# Mesure.net
KiCad netlist of a schematic drawn in Altium Designer
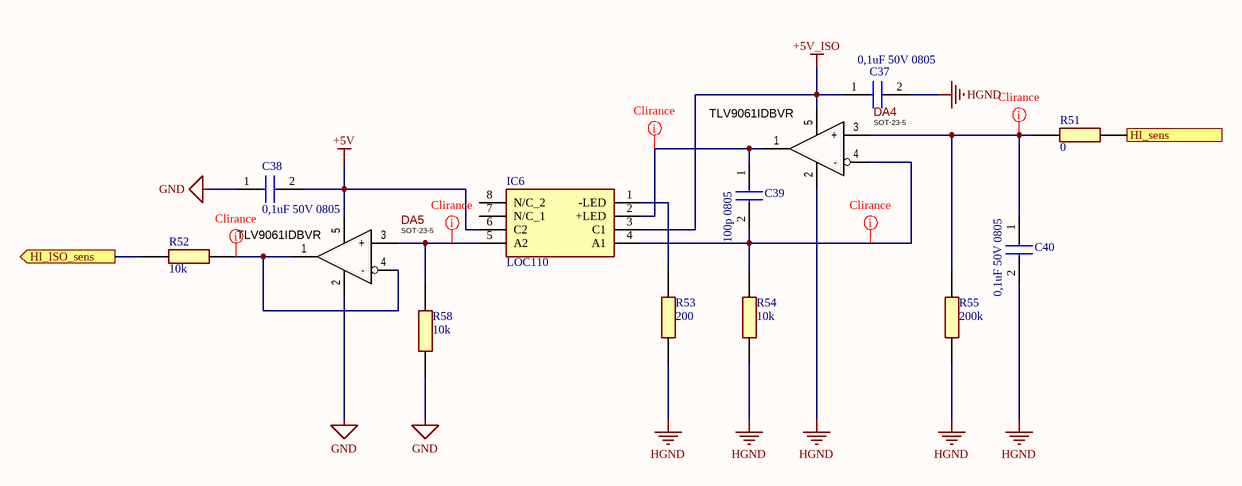
[diagram p0: Mesure.SchDoc]

(export (version "E")
  (design (tool "Eeschema 10.0.6"))
  (components
    (comp (ref "C37")
      (value "0,1uF 50V 0805")
      (footprint "SamacSys:CAPC2012X90N")
      (description "Capacitor")
      (libsource (lib "*") (part "MCMT21N470F250CT"))
    )
    (comp (ref "C38")
      (value "0,1uF 50V 0805")
      (footprint "SamacSys:CAPC2012X90N")
      (description "Capacitor")
      (libsource (lib "*") (part "MCMT21N470F250CT"))
    )
    (comp (ref "C39")
      (value "100p 0805")
      (footprint "SamacSys:CAPC2012X90N")
      (description "Capacitor")
      (libsource (lib "*") (part "MCMT21N470F250CT"))
    )
    (comp (ref "C40")
      (value "0,1uF 50V 0805")
      (footprint "SamacSys:CAPC2012X90N")
      (description "Capacitor")
      (libsource (lib "*") (part "MCMT21N470F250CT"))
    )
    (comp (ref "DA4")
      (value "TLV9061IDBVR")
      (footprint "SOT-23-5")
      (fields
        (field (name "PACKAGE") "SOT-23-5")
        (field (name "PART NUMBER") "TLV9061IDBVR")
        (field (name "MANUFACTURER") "Texas Instruments")
      )
      (libsource (lib "AjaxLibrary") (part "TLV90x1IDBVR"))
    )
    (comp (ref "DA5")
      (value "TLV9061IDBVR")
      (footprint "SOT-23-5")
      (fields
        (field (name "PACKAGE") "SOT-23-5")
        (field (name "PART NUMBER") "TLV9061IDBVR")
        (field (name "MANUFACTURER") "Texas Instruments")
      )
      (libsource (lib "AjaxLibrary") (part "TLV90x1IDBVR"))
    )
    (comp (ref "IC6")
      (value "LOC110")
      (footprint "SamacSys:DIP762W53P254L965H335Q8N")
      (description "Integrated Circuit")
      (fields (field (name "MOUSER PART NUMBER") "849-LOC110"))
      (libsource (lib "SamacSys") (part "LOC110"))
    )
    (comp (ref "R51")
      (value "0")
      (footprint "RESC2013X65N")
      (description "Resistor")
      (libsource (lib "SamacSys") (part "ERJP06J822V"))
    )
    (comp (ref "R52")
      (value "10k")
      (footprint "RESC2013X65N")
      (description "Resistor")
      (libsource (lib "SamacSys") (part "ERJP06J822V"))
    )
    (comp (ref "R53")
      (value "200")
      (footprint "RESC2013X65N")
      (description "Resistor")
      (libsource (lib "") (part "ERJP06J822V_1"))
    )
    (comp (ref "R54")
      (value "10k")
      (footprint "RESC2013X65N")
      (description "Resistor")
      (libsource (lib "") (part "ERJP06J822V_1"))
    )
    (comp (ref "R55")
      (value "200k")
      (footprint "RESC2013X65N")
      (description "Resistor")
      (libsource (lib "") (part "ERJP06J822V_1"))
    )
    (comp (ref "R58")
      (value "10k")
      (footprint "RESC2013X65N")
      (description "Resistor")
      (libsource (lib "") (part "ERJP06J822V_1"))
    )
  )
  (nets
    (net (code "1") (name "+5V") (class "Default")
      (node (ref "C38") (pin "2") (pinfunction "2_2") (pintype "passive"))
      (node (ref "DA5") (pin "5") (pinfunction "V+_5") (pintype "passive"))
      (node (ref "IC6") (pin "6") (pinfunction "C2_6") (pintype "passive"))
    )
    (net (code "2") (name "+5V_ISO") (class "Default")
      (node (ref "C37") (pin "1") (pinfunction "1_1") (pintype "passive"))
      (node (ref "DA4") (pin "5") (pinfunction "V+_5") (pintype "passive"))
      (node (ref "IC6") (pin "3") (pinfunction "C1_3") (pintype "passive"))
    )
    (net (code "3") (name "/HI_ISO_sens") (class "Default")
      (node (ref "R52") (pin "2") (pinfunction "2_2") (pintype "passive"))
    )
    (net (code "4") (name "/HI_sens") (class "Default")
      (node (ref "R51") (pin "1") (pinfunction "1_1") (pintype "passive"))
    )
    (net (code "5") (name "GND") (class "Default")
      (node (ref "C38") (pin "1") (pinfunction "1_1") (pintype "passive"))
      (node (ref "DA5") (pin "2") (pinfunction "V-_2") (pintype "passive"))
      (node (ref "R58") (pin "1") (pinfunction "1_1") (pintype "passive"))
    )
    (net (code "6") (name "HGND") (class "Default")
      (node (ref "C37") (pin "2") (pinfunction "2_2") (pintype "passive"))
      (node (ref "C40") (pin "2") (pinfunction "2_2") (pintype "passive"))
      (node (ref "DA4") (pin "2") (pinfunction "V-_2") (pintype "passive"))
      (node (ref "R53") (pin "1") (pinfunction "1_1") (pintype "passive"))
      (node (ref "R54") (pin "1") (pinfunction "1_1") (pintype "passive"))
      (node (ref "R55") (pin "1") (pinfunction "1_1") (pintype "passive"))
    )
    (net (code "7") (name "Net-(DA4-+)") (class "Default")
      (node (ref "C40") (pin "1") (pinfunction "1_1") (pintype "passive"))
      (node (ref "DA4") (pin "3") (pinfunction "+_3") (pintype "passive"))
      (node (ref "R51") (pin "2") (pinfunction "2_2") (pintype "passive"))
      (node (ref "R55") (pin "2") (pinfunction "2_2") (pintype "passive"))
    )
    (net (code "8") (name "Net-(DA4--)") (class "Default")
      (node (ref "C39") (pin "2") (pinfunction "2_2") (pintype "passive"))
      (node (ref "DA4") (pin "4") (pinfunction "-_4") (pintype "passive"))
      (node (ref "IC6") (pin "4") (pinfunction "A1_4") (pintype "passive"))
      (node (ref "R54") (pin "2") (pinfunction "2_2") (pintype "passive"))
    )
    (net (code "9") (name "Net-(DA4-OUT)") (class "Default")
      (node (ref "C39") (pin "1") (pinfunction "1_1") (pintype "passive"))
      (node (ref "DA4") (pin "1") (pinfunction "OUT_1") (pintype "passive"))
      (node (ref "IC6") (pin "2") (pinfunction "+LED_2") (pintype "passive"))
    )
    (net (code "10") (name "Net-(DA5-+)") (class "Default")
      (node (ref "DA5") (pin "3") (pinfunction "+_3") (pintype "passive"))
      (node (ref "IC6") (pin "5") (pinfunction "A2_5") (pintype "passive"))
      (node (ref "R58") (pin "2") (pinfunction "2_2") (pintype "passive"))
    )
    (net (code "11") (name "Net-(DA5--)") (class "Default")
      (node (ref "DA5") (pin "1") (pinfunction "OUT_1") (pintype "passive"))
      (node (ref "DA5") (pin "4") (pinfunction "-_4") (pintype "passive"))
      (node (ref "R52") (pin "1") (pinfunction "1_1") (pintype "passive"))
    )
    (net (code "12") (name "Net-(IC6--LED)") (class "Default")
      (node (ref "IC6") (pin "1") (pinfunction "-LED_1") (pintype "passive"))
      (node (ref "R53") (pin "2") (pinfunction "2_2") (pintype "passive"))
    )
    (net (code "13") (name "unconnected-(IC6-N{slash}C_1-Pad7)") (class "Default")
      (node (ref "IC6") (pin "7") (pinfunction "N/C_1_7") (pintype "passive"))
    )
    (net (code "14") (name "unconnected-(IC6-N{slash}C_2-Pad8)") (class "Default")
      (node (ref "IC6") (pin "8") (pinfunction "N/C_2_8") (pintype "passive"))
    )
  )
)
